# design.net
KiCad netlist of a schematic drawn in Altium Designer
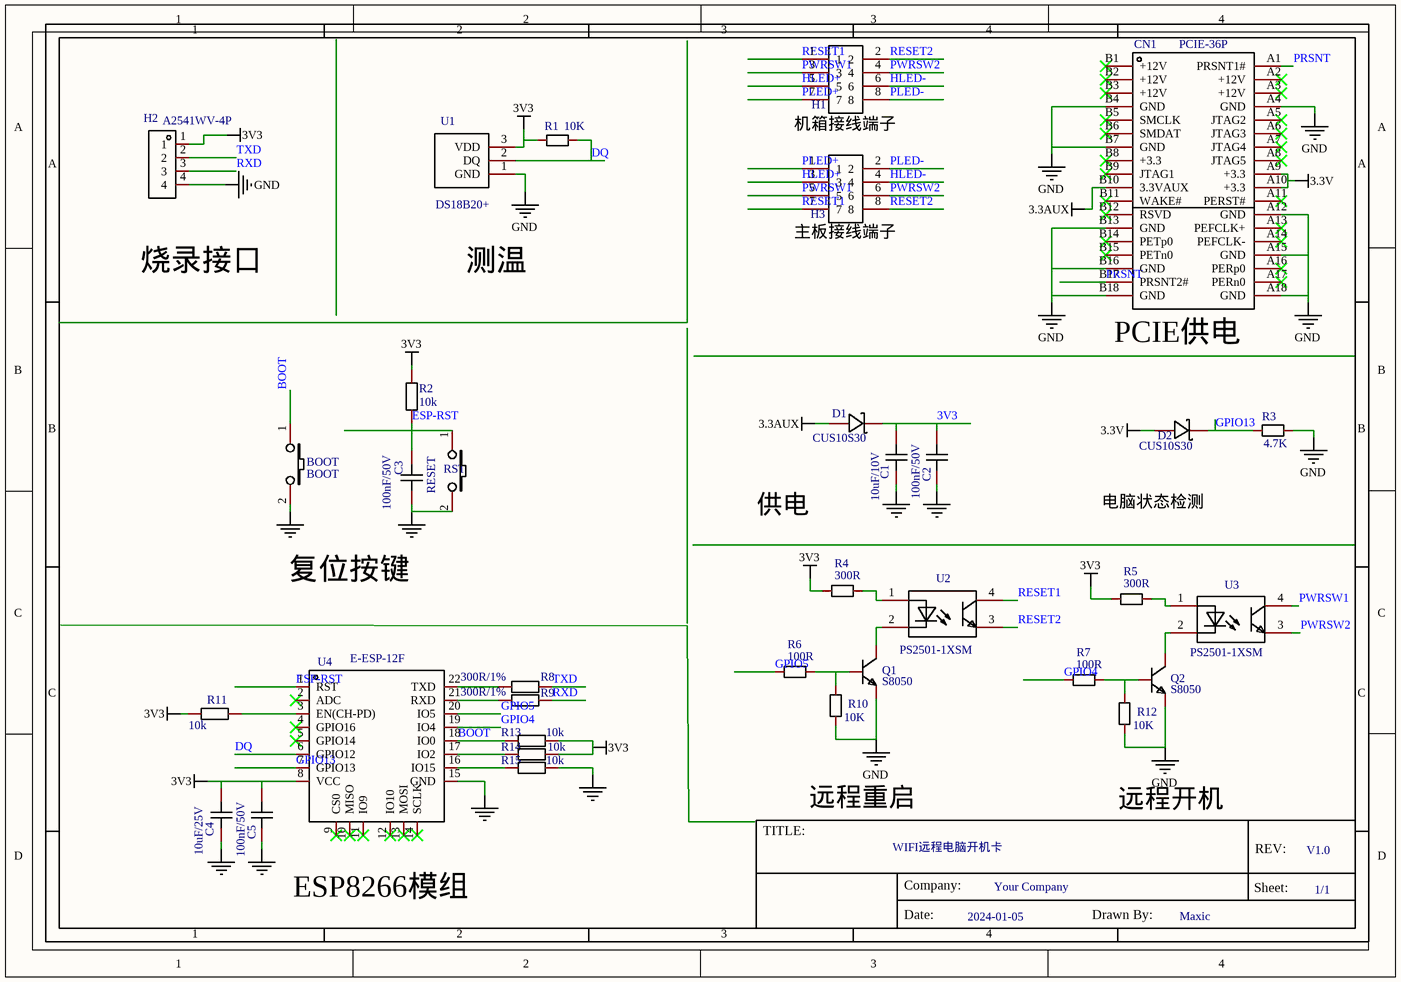
[diagram p0: 远程开机卡.schdoc]

(export (version "E")
  (design (tool "Eeschema 10.0.6"))
  (components
    (comp (ref "BOOT")
      (value "BOOT")
      (fields
        (field (name "NAME") "BOOT")
        (field (name "MANUFACTURER") "HRO")
        (field (name "MANUFACTURER PART") "K2-1107ST")
      )
      (libsource (lib "altium-import") (part "root_3_BOOT_"))
    )
    (comp (ref "C1")
      (value "10uF/10V")
      (fields
        (field (name "NAME") "10uF/10V")
        (field (name "MANUFACTURER") "Murata Electronics")
        (field (name "MANUFACTURER PART") "GRM188B31A106ME69D")
      )
      (libsource (lib "altium-import") (part "root_1_10uF/10V_"))
    )
    (comp (ref "C2")
      (value "100nF/50V")
      (fields
        (field (name "NAME") "100nF/50V")
        (field (name "MANUFACTURER") "Darfon Elec")
        (field (name "MANUFACTURER PART") "C1608X7R104KGTS")
      )
      (libsource (lib "altium-import") (part "root_1_100nF/50V_"))
    )
    (comp (ref "C3")
      (value "100nF/50V")
      (fields
        (field (name "NAME") "100nF/50V")
        (field (name "MANUFACTURER") "Darfon Elec")
        (field (name "MANUFACTURER PART") "C1608X7R104KGTS")
      )
      (libsource (lib "altium-import") (part "root_1_100nF/50V_"))
    )
    (comp (ref "C4")
      (value "10uF/25V")
      (fields
        (field (name "NAME") "10uF/25V")
        (field (name "MANUFACTURER") "TDK")
        (field (name "MANUFACTURER PART") "C1608X5R1E106MT000E")
      )
      (libsource (lib "altium-import") (part "root_1_10uF/25V_"))
    )
    (comp (ref "C5")
      (value "100nF/50V")
      (fields
        (field (name "NAME") "100nF/50V")
        (field (name "MANUFACTURER") "Darfon Elec")
        (field (name "MANUFACTURER PART") "C1608X7R104KGTS")
      )
      (libsource (lib "altium-import") (part "root_1_100nF/50V_"))
    )
    (comp (ref "CN1")
      (value "PCIE-36P")
      (fields (field (name "NAME") "PCIE-36P") (field (name "MANUFACTURER") "UMAX"))
      (libsource (lib "altium-import") (part "root_0_PCIE-36P_"))
    )
    (comp (ref "D1")
      (value "CUS10S30")
      (fields
        (field (name "NAME") "CUS10S30")
        (field (name "MANUFACTURER") "TOSHIBA")
        (field (name "MANUFACTURER PART") "CUS10S30 H3F")
      )
      (libsource (lib "altium-import") (part "root_2_CUS10S30_"))
    )
    (comp (ref "D2")
      (value "CUS10S30")
      (fields
        (field (name "NAME") "CUS10S30")
        (field (name "MANUFACTURER") "TOSHIBA")
        (field (name "MANUFACTURER PART") "CUS10S30 H3F")
      )
      (libsource (lib "altium-import") (part "root_2_CUS10S30_"))
    )
    (comp (ref "H1")
      (value "机箱接线端子")
      (fields (field (name "MANUFACTURER") "Shenzhen Cankemeng"))
      (libsource (lib "altium-import") (part "root_0_机箱接线端子_"))
    )
    (comp (ref "H2")
      (value "A2541WV-4P")
      (fields (field (name "NAME") "A2541WV-4P") (field (name "MANUFACTURER") "CJT(长江连接器)"))
      (libsource (lib "altium-import") (part "root_1_A2541WV-4P_"))
    )
    (comp (ref "H3")
      (value "主板接线端子")
      (fields (field (name "MANUFACTURER") "Shenzhen Cankemeng"))
      (libsource (lib "altium-import") (part "root_0_主板接线端子_"))
    )
    (comp (ref "Q1")
      (value "S8050")
      (fields (field (name "NAME") "S8050") (field (name "MANUFACTURER") "CJ"))
      (libsource (lib "altium-import") (part "root_0_S8050_"))
    )
    (comp (ref "Q2")
      (value "S8050")
      (fields (field (name "NAME") "S8050") (field (name "MANUFACTURER") "CJ"))
      (libsource (lib "altium-import") (part "root_0_S8050_"))
    )
    (comp (ref "R1")
      (value "10K")
      (fields (field (name "NAME") "10K") (field (name "MANUFACTURER") "ResistorToday"))
      (libsource (lib "altium-import") (part "root_2_10K_"))
    )
    (comp (ref "R2")
      (value "10k")
      (fields
        (field (name "NAME") "10k")
        (field (name "MANUFACTURER") "KOA Speer Elec")
        (field (name "MANUFACTURER PART") "RK73G1JTTD1002F")
      )
      (libsource (lib "altium-import") (part "root_3_10k/1%_"))
    )
    (comp (ref "R3")
      (value "4.7K")
      (fields (field (name "NAME") "4.7K") (field (name "MANUFACTURER") "PANASONIC"))
      (libsource (lib "altium-import") (part "root_0_4.7K_"))
    )
    (comp (ref "R4")
      (value "300R")
      (fields (field (name "NAME") "300R") (field (name "MANUFACTURER") "ResistorToday"))
      (libsource (lib "altium-import") (part "root_0_300R_"))
    )
    (comp (ref "R5")
      (value "300R")
      (fields (field (name "NAME") "300R") (field (name "MANUFACTURER") "ResistorToday"))
      (libsource (lib "altium-import") (part "root_0_300R_"))
    )
    (comp (ref "R6")
      (value "100R")
      (fields (field (name "NAME") "100R") (field (name "MANUFACTURER") "YAGEO"))
      (libsource (lib "altium-import") (part "root_0_100R_"))
    )
    (comp (ref "R7")
      (value "100R")
      (fields (field (name "NAME") "100R") (field (name "MANUFACTURER") "YAGEO"))
      (libsource (lib "altium-import") (part "root_0_100R_"))
    )
    (comp (ref "R8")
      (value "300R/1%")
      (fields
        (field (name "NAME") "300R/1%")
        (field (name "MANUFACTURER") "YAGEO")
        (field (name "MANUFACTURER PART") "AC0603FR-07300RL")
      )
      (libsource (lib "altium-import") (part "root_2_300R/1%_"))
    )
    (comp (ref "R9")
      (value "300R/1%")
      (fields
        (field (name "NAME") "300R/1%")
        (field (name "MANUFACTURER") "YAGEO")
        (field (name "MANUFACTURER PART") "AC0603FR-07300RL")
      )
      (libsource (lib "altium-import") (part "root_2_300R/1%_"))
    )
    (comp (ref "R10")
      (value "10K")
      (fields (field (name "NAME") "10K") (field (name "MANUFACTURER") "Stackpole Elec"))
      (libsource (lib "altium-import") (part "root_3_10K_"))
    )
    (comp (ref "R11")
      (value "10k")
      (fields
        (field (name "NAME") "10k")
        (field (name "MANUFACTURER") "KOA Speer Elec")
        (field (name "MANUFACTURER PART") "RK73G1JTTD1002F")
      )
      (libsource (lib "altium-import") (part "root_2_10k/1%_"))
    )
    (comp (ref "R12")
      (value "10K")
      (fields (field (name "NAME") "10K") (field (name "MANUFACTURER") "Stackpole Elec"))
      (libsource (lib "altium-import") (part "root_3_10K_"))
    )
    (comp (ref "R13")
      (value "10k")
      (fields
        (field (name "NAME") "10k")
        (field (name "MANUFACTURER") "KOA Speer Elec")
        (field (name "MANUFACTURER PART") "RK73G1JTTD1002F")
      )
      (libsource (lib "altium-import") (part "root_0_10k/1%_"))
    )
    (comp (ref "R14")
      (value "10k")
      (fields
        (field (name "NAME") "10k")
        (field (name "MANUFACTURER") "KOA Speer Elec")
        (field (name "MANUFACTURER PART") "RK73G1JTTD1002F")
      )
      (libsource (lib "altium-import") (part "root_2_10k/1%_"))
    )
    (comp (ref "R15")
      (value "10k")
      (fields
        (field (name "NAME") "10k")
        (field (name "MANUFACTURER") "KOA Speer Elec")
        (field (name "MANUFACTURER PART") "RK73G1JTTD1002F")
      )
      (libsource (lib "altium-import") (part "root_2_10k/1%_"))
    )
    (comp (ref "RST")
      (value "RESET")
      (fields
        (field (name "NAME") "RESET")
        (field (name "MANUFACTURER") "HRO")
        (field (name "MANUFACTURER PART") "K2-1107ST")
      )
      (libsource (lib "altium-import") (part "root_3_RESET_"))
    )
    (comp (ref "U1")
      (value "DS18B20+")
      (fields (field (name "NAME") "DS18B20+") (field (name "MANUFACTURER") "ADI(亚德诺)/MAXIM(美信)"))
      (libsource (lib "altium-import") (part "root_2_DS18B20+_"))
    )
    (comp (ref "U2")
      (value "PS2501-1XSM")
      (fields (field (name "NAME") "PS2501-1XSM") (field (name "MANUFACTURER") "ISOCOM(英国安数光)"))
      (libsource (lib "altium-import") (part "root_0_PS2501-1XSM_"))
    )
    (comp (ref "U3")
      (value "PS2501-1XSM")
      (fields (field (name "NAME") "PS2501-1XSM") (field (name "MANUFACTURER") "ISOCOM(英国安数光)"))
      (libsource (lib "altium-import") (part "root_0_PS2501-1XSM_"))
    )
    (comp (ref "U4")
      (value "E-ESP-12F")
      (fields
        (field (name "NAME") "E-ESP-12F")
        (field (name "MANUFACTURER PART") "ESP-12F(ESP8266MOD)")
        (field (name "MANUFACTURER") "Ai-Thinker")
      )
      (libsource (lib "altium-import") (part "root_0_E-ESP-12F_"))
    )
  )
  (nets
    (net (code "1") (name "/BOOT") (class "Default")
      (node (ref "BOOT") (pin "1") (pinfunction "1_1") (pintype "passive"))
      (node (ref "R13") (pin "1") (pinfunction "1_1") (pintype "passive"))
      (node (ref "U4") (pin "18") (pinfunction "IO0_18") (pintype "passive"))
    )
    (net (code "2") (name "/DQ") (class "Default")
      (node (ref "R1") (pin "1") (pinfunction "1_1") (pintype "passive"))
      (node (ref "U1") (pin "2") (pinfunction "DQ_2") (pintype "passive"))
      (node (ref "U4") (pin "6") (pinfunction "GPIO12_6") (pintype "passive"))
    )
    (net (code "3") (name "/ESP-RST") (class "Default")
      (node (ref "C3") (pin "2") (pinfunction "2_2") (pintype "passive"))
      (node (ref "R2") (pin "2") (pinfunction "2_2") (pintype "passive"))
      (node (ref "RST") (pin "1") (pinfunction "1_1") (pintype "passive"))
      (node (ref "U4") (pin "1") (pinfunction "RST_1") (pintype "passive"))
    )
    (net (code "4") (name "/GPIO4") (class "Default")
      (node (ref "R7") (pin "1") (pinfunction "1_1") (pintype "passive"))
      (node (ref "U4") (pin "19") (pinfunction "IO4_19") (pintype "passive"))
    )
    (net (code "5") (name "/GPIO5") (class "Default")
      (node (ref "R6") (pin "1") (pinfunction "1_1") (pintype "passive"))
      (node (ref "U4") (pin "20") (pinfunction "IO5_20") (pintype "passive"))
    )
    (net (code "6") (name "/GPIO13") (class "Default")
      (node (ref "D2") (pin "1") (pinfunction "K_1") (pintype "passive"))
      (node (ref "R3") (pin "1") (pinfunction "1_1") (pintype "passive"))
      (node (ref "U4") (pin "7") (pinfunction "GPIO13_7") (pintype "passive"))
    )
    (net (code "7") (name "/HLED+") (class "Default")
      (node (ref "H1") (pin "5") (pinfunction "5_5") (pintype "passive"))
      (node (ref "H3") (pin "3") (pinfunction "3_3") (pintype "passive"))
    )
    (net (code "8") (name "/HLED-") (class "Default")
      (node (ref "H1") (pin "6") (pinfunction "6_6") (pintype "passive"))
      (node (ref "H3") (pin "4") (pinfunction "4_4") (pintype "passive"))
    )
    (net (code "9") (name "/PLED+") (class "Default")
      (node (ref "H1") (pin "7") (pinfunction "7_7") (pintype "passive"))
      (node (ref "H3") (pin "1") (pinfunction "1_1") (pintype "passive"))
    )
    (net (code "10") (name "/PLED-") (class "Default")
      (node (ref "H1") (pin "8") (pinfunction "8_8") (pintype "passive"))
      (node (ref "H3") (pin "2") (pinfunction "2_2") (pintype "passive"))
    )
    (net (code "11") (name "/PRSNT") (class "Default")
      (node (ref "CN1") (pin "A1") (pinfunction "PRSNT1#_A1") (pintype "passive"))
      (node (ref "CN1") (pin "B17") (pinfunction "PRSNT2#_B17") (pintype "passive"))
    )
    (net (code "12") (name "/PWRSW1") (class "Default")
      (node (ref "H1") (pin "3") (pinfunction "3_3") (pintype "passive"))
      (node (ref "H3") (pin "5") (pinfunction "5_5") (pintype "passive"))
      (node (ref "U3") (pin "4") (pinfunction "Collector_4") (pintype "passive"))
    )
    (net (code "13") (name "/PWRSW2") (class "Default")
      (node (ref "H1") (pin "4") (pinfunction "4_4") (pintype "passive"))
      (node (ref "H3") (pin "6") (pinfunction "6_6") (pintype "passive"))
      (node (ref "U3") (pin "3") (pinfunction "Emitter_3") (pintype "passive"))
    )
    (net (code "14") (name "/RESET1") (class "Default")
      (node (ref "H1") (pin "1") (pinfunction "1_1") (pintype "passive"))
      (node (ref "H3") (pin "7") (pinfunction "7_7") (pintype "passive"))
      (node (ref "U2") (pin "4") (pinfunction "Collector_4") (pintype "passive"))
    )
    (net (code "15") (name "/RESET2") (class "Default")
      (node (ref "H1") (pin "2") (pinfunction "2_2") (pintype "passive"))
      (node (ref "H3") (pin "8") (pinfunction "8_8") (pintype "passive"))
      (node (ref "U2") (pin "3") (pinfunction "Emitter_3") (pintype "passive"))
    )
    (net (code "16") (name "/RXD") (class "Default")
      (node (ref "H2") (pin "3") (pinfunction "3_3") (pintype "passive"))
      (node (ref "R9") (pin "1") (pinfunction "1_1") (pintype "passive"))
    )
    (net (code "17") (name "/TXD") (class "Default")
      (node (ref "H2") (pin "2") (pinfunction "2_2") (pintype "passive"))
      (node (ref "R8") (pin "1") (pinfunction "1_1") (pintype "passive"))
    )
    (net (code "18") (name "3.3AUX") (class "Default")
      (node (ref "CN1") (pin "B10") (pinfunction "3.3VAUX_B10") (pintype "passive"))
      (node (ref "D1") (pin "2") (pinfunction "A_2") (pintype "passive"))
    )
    (net (code "19") (name "3.3V") (class "Default")
      (node (ref "CN1") (pin "A10") (pinfunction "+3.3_A10") (pintype "passive"))
      (node (ref "CN1") (pin "A9") (pinfunction "+3.3_A9") (pintype "passive"))
      (node (ref "D2") (pin "2") (pinfunction "A_2") (pintype "passive"))
    )
    (net (code "20") (name "3V3") (class "Default")
      (node (ref "C1") (pin "2") (pinfunction "2_2") (pintype "passive"))
      (node (ref "C2") (pin "2") (pinfunction "2_2") (pintype "passive"))
      (node (ref "C4") (pin "2") (pinfunction "2_2") (pintype "passive"))
      (node (ref "C5") (pin "2") (pinfunction "2_2") (pintype "passive"))
      (node (ref "D1") (pin "1") (pinfunction "K_1") (pintype "passive"))
      (node (ref "H2") (pin "1") (pinfunction "1_1") (pintype "passive"))
      (node (ref "R1") (pin "2") (pinfunction "2_2") (pintype "passive"))
      (node (ref "R11") (pin "2") (pinfunction "2_2") (pintype "passive"))
      (node (ref "R13") (pin "2") (pinfunction "2_2") (pintype "passive"))
      (node (ref "R14") (pin "1") (pinfunction "1_1") (pintype "passive"))
      (node (ref "R2") (pin "1") (pinfunction "1_1") (pintype "passive"))
      (node (ref "R4") (pin "1") (pinfunction "1_1") (pintype "passive"))
      (node (ref "R5") (pin "1") (pinfunction "1_1") (pintype "passive"))
      (node (ref "U1") (pin "3") (pinfunction "VDD_3") (pintype "passive"))
      (node (ref "U4") (pin "8") (pinfunction "VCC_8") (pintype "passive"))
    )
    (net (code "21") (name "GND") (class "Default")
      (node (ref "BOOT") (pin "2") (pinfunction "2_2") (pintype "passive"))
      (node (ref "C1") (pin "1") (pinfunction "1_1") (pintype "passive"))
      (node (ref "C2") (pin "1") (pinfunction "1_1") (pintype "passive"))
      (node (ref "C3") (pin "1") (pinfunction "1_1") (pintype "passive"))
      (node (ref "C4") (pin "1") (pinfunction "1_1") (pintype "passive"))
      (node (ref "C5") (pin "1") (pinfunction "1_1") (pintype "passive"))
      (node (ref "CN1") (pin "A12") (pinfunction "GND_A12") (pintype "passive"))
      (node (ref "CN1") (pin "A15") (pinfunction "GND_A15") (pintype "passive"))
      (node (ref "CN1") (pin "A18") (pinfunction "GND_A18") (pintype "passive"))
      (node (ref "CN1") (pin "A4") (pinfunction "GND_A4") (pintype "passive"))
      (node (ref "CN1") (pin "B13") (pinfunction "GND_B13") (pintype "passive"))
      (node (ref "CN1") (pin "B16") (pinfunction "GND_B16") (pintype "passive"))
      (node (ref "CN1") (pin "B18") (pinfunction "GND_B18") (pintype "passive"))
      (node (ref "CN1") (pin "B4") (pinfunction "GND_B4") (pintype "passive"))
      (node (ref "CN1") (pin "B7") (pinfunction "GND_B7") (pintype "passive"))
      (node (ref "H2") (pin "4") (pinfunction "4_4") (pintype "passive"))
      (node (ref "Q1") (pin "2") (pinfunction "2_2") (pintype "passive"))
      (node (ref "Q2") (pin "2") (pinfunction "2_2") (pintype "passive"))
      (node (ref "R10") (pin "2") (pinfunction "2_2") (pintype "passive"))
      (node (ref "R12") (pin "2") (pinfunction "2_2") (pintype "passive"))
      (node (ref "R15") (pin "1") (pinfunction "1_1") (pintype "passive"))
      (node (ref "R3") (pin "2") (pinfunction "2_2") (pintype "passive"))
      (node (ref "RST") (pin "2") (pinfunction "2_2") (pintype "passive"))
      (node (ref "U1") (pin "1") (pinfunction "GND_1") (pintype "passive"))
      (node (ref "U4") (pin "15") (pinfunction "GND_15") (pintype "passive"))
    )
    (net (code "22") (name "Net-(Q1-Pad1)") (class "Default")
      (node (ref "Q1") (pin "1") (pinfunction "1_1") (pintype "passive"))
      (node (ref "R10") (pin "1") (pinfunction "1_1") (pintype "passive"))
      (node (ref "R6") (pin "2") (pinfunction "2_2") (pintype "passive"))
    )
    (net (code "23") (name "Net-(Q2-Pad1)") (class "Default")
      (node (ref "Q2") (pin "1") (pinfunction "1_1") (pintype "passive"))
      (node (ref "R12") (pin "1") (pinfunction "1_1") (pintype "passive"))
      (node (ref "R7") (pin "2") (pinfunction "2_2") (pintype "passive"))
    )
    (net (code "24") (name "Net-(U2-Anode)") (class "Default")
      (node (ref "R4") (pin "2") (pinfunction "2_2") (pintype "passive"))
      (node (ref "U2") (pin "1") (pinfunction "Anode_1") (pintype "passive"))
    )
    (net (code "25") (name "Net-(U2-Cathode)") (class "Default")
      (node (ref "Q1") (pin "3") (pinfunction "3_3") (pintype "passive"))
      (node (ref "U2") (pin "2") (pinfunction "Cathode_2") (pintype "passive"))
    )
    (net (code "26") (name "Net-(U3-Anode)") (class "Default")
      (node (ref "R5") (pin "2") (pinfunction "2_2") (pintype "passive"))
      (node (ref "U3") (pin "1") (pinfunction "Anode_1") (pintype "passive"))
    )
    (net (code "27") (name "Net-(U3-Cathode)") (class "Default")
      (node (ref "Q2") (pin "3") (pinfunction "3_3") (pintype "passive"))
      (node (ref "U3") (pin "2") (pinfunction "Cathode_2") (pintype "passive"))
    )
    (net (code "28") (name "Net-(U4-EN(CH-PD))") (class "Default")
      (node (ref "R11") (pin "1") (pinfunction "1_1") (pintype "passive"))
      (node (ref "U4") (pin "3") (pinfunction "EN(CH-PD)_3") (pintype "passive"))
    )
    (net (code "29") (name "Net-(U4-IO2)") (class "Default")
      (node (ref "R14") (pin "2") (pinfunction "2_2") (pintype "passive"))
      (node (ref "U4") (pin "17") (pinfunction "IO2_17") (pintype "passive"))
    )
    (net (code "30") (name "Net-(U4-IO15)") (class "Default")
      (node (ref "R15") (pin "2") (pinfunction "2_2") (pintype "passive"))
      (node (ref "U4") (pin "16") (pinfunction "IO15_16") (pintype "passive"))
    )
    (net (code "31") (name "Net-(U4-RXD)") (class "Default")
      (node (ref "R9") (pin "2") (pinfunction "2_2") (pintype "passive"))
      (node (ref "U4") (pin "21") (pinfunction "RXD_21") (pintype "passive"))
    )
    (net (code "32") (name "Net-(U4-TXD)") (class "Default")
      (node (ref "R8") (pin "2") (pinfunction "2_2") (pintype "passive"))
      (node (ref "U4") (pin "22") (pinfunction "TXD_22") (pintype "passive"))
    )
    (net (code "33") (name "unconnected-(CN1-+3.3-PadB8)") (class "Default")
      (node (ref "CN1") (pin "B8") (pinfunction "+3.3_B8") (pintype "passive+no_connect"))
    )
    (net (code "34") (name "unconnected-(CN1-+12V-PadA2)") (class "Default")
      (node (ref "CN1") (pin "A2") (pinfunction "+12V_A2") (pintype "passive+no_connect"))
    )
    (net (code "35") (name "unconnected-(CN1-+12V-PadA3)") (class "Default")
      (node (ref "CN1") (pin "A3") (pinfunction "+12V_A3") (pintype "passive+no_connect"))
    )
    (net (code "36") (name "unconnected-(CN1-+12V-PadB1)") (class "Default")
      (node (ref "CN1") (pin "B1") (pinfunction "+12V_B1") (pintype "passive+no_connect"))
    )
    (net (code "37") (name "unconnected-(CN1-+12V-PadB2)") (class "Default")
      (node (ref "CN1") (pin "B2") (pinfunction "+12V_B2") (pintype "passive+no_connect"))
    )
    (net (code "38") (name "unconnected-(CN1-+12V-PadB3)") (class "Default")
      (node (ref "CN1") (pin "B3") (pinfunction "+12V_B3") (pintype "passive+no_connect"))
    )
    (net (code "39") (name "unconnected-(CN1-JTAG1-PadB9)") (class "Default")
      (node (ref "CN1") (pin "B9") (pinfunction "JTAG1_B9") (pintype "passive+no_connect"))
    )
    (net (code "40") (name "unconnected-(CN1-JTAG2-PadA5)") (class "Default")
      (node (ref "CN1") (pin "A5") (pinfunction "JTAG2_A5") (pintype "passive+no_connect"))
    )
    (net (code "41") (name "unconnected-(CN1-JTAG3-PadA6)") (class "Default")
      (node (ref "CN1") (pin "A6") (pinfunction "JTAG3_A6") (pintype "passive+no_connect"))
    )
    (net (code "42") (name "unconnected-(CN1-JTAG4-PadA7)") (class "Default")
      (node (ref "CN1") (pin "A7") (pinfunction "JTAG4_A7") (pintype "passive+no_connect"))
    )
    (net (code "43") (name "unconnected-(CN1-JTAG5-PadA8)") (class "Default")
      (node (ref "CN1") (pin "A8") (pinfunction "JTAG5_A8") (pintype "passive+no_connect"))
    )
    (net (code "44") (name "unconnected-(CN1-PEFCLK+-PadA13)") (class "Default")
      (node (ref "CN1") (pin "A13") (pinfunction "PEFCLK+_A13") (pintype "passive+no_connect"))
    )
    (net (code "45") (name "unconnected-(CN1-PEFCLK--PadA14)") (class "Default")
      (node (ref "CN1") (pin "A14") (pinfunction "PEFCLK-_A14") (pintype "passive+no_connect"))
    )
    (net (code "46") (name "unconnected-(CN1-PERST#-PadA11)") (class "Default")
      (node (ref "CN1") (pin "A11") (pinfunction "PERST#_A11") (pintype "passive+no_connect"))
    )
    (net (code "47") (name "unconnected-(CN1-PERn0-PadA17)") (class "Default")
      (node (ref "CN1") (pin "A17") (pinfunction "PERn0_A17") (pintype "passive+no_connect"))
    )
    (net (code "48") (name "unconnected-(CN1-PERp0-PadA16)") (class "Default")
      (node (ref "CN1") (pin "A16") (pinfunction "PERp0_A16") (pintype "passive+no_connect"))
    )
    (net (code "49") (name "unconnected-(CN1-PETn0-PadB15)") (class "Default")
      (node (ref "CN1") (pin "B15") (pinfunction "PETn0_B15") (pintype "passive+no_connect"))
    )
    (net (code "50") (name "unconnected-(CN1-PETp0-PadB14)") (class "Default")
      (node (ref "CN1") (pin "B14") (pinfunction "PETp0_B14") (pintype "passive+no_connect"))
    )
    (net (code "51") (name "unconnected-(CN1-RSVD-PadB12)") (class "Default")
      (node (ref "CN1") (pin "B12") (pinfunction "RSVD_B12") (pintype "passive+no_connect"))
    )
    (net (code "52") (name "unconnected-(CN1-SMCLK-PadB5)") (class "Default")
      (node (ref "CN1") (pin "B5") (pinfunction "SMCLK_B5") (pintype "passive+no_connect"))
    )
    (net (code "53") (name "unconnected-(CN1-SMDAT-PadB6)") (class "Default")
      (node (ref "CN1") (pin "B6") (pinfunction "SMDAT_B6") (pintype "passive+no_connect"))
    )
    (net (code "54") (name "unconnected-(CN1-WAKE#-PadB11)") (class "Default")
      (node (ref "CN1") (pin "B11") (pinfunction "WAKE#_B11") (pintype "passive+no_connect"))
    )
    (net (code "55") (name "unconnected-(U4-ADC-Pad2)") (class "Default")
      (node (ref "U4") (pin "2") (pinfunction "ADC_2") (pintype "passive+no_connect"))
    )
    (net (code "56") (name "unconnected-(U4-CS0-Pad9)") (class "Default")
      (node (ref "U4") (pin "9") (pinfunction "CS0_9") (pintype "passive+no_connect"))
    )
    (net (code "57") (name "unconnected-(U4-GPIO14-Pad5)") (class "Default")
      (node (ref "U4") (pin "5") (pinfunction "GPIO14_5") (pintype "passive+no_connect"))
    )
    (net (code "58") (name "unconnected-(U4-GPIO16-Pad4)") (class "Default")
      (node (ref "U4") (pin "4") (pinfunction "GPIO16_4") (pintype "passive+no_connect"))
    )
    (net (code "59") (name "unconnected-(U4-IO9-Pad11)") (class "Default")
      (node (ref "U4") (pin "11") (pinfunction "IO9_11") (pintype "passive+no_connect"))
    )
    (net (code "60") (name "unconnected-(U4-IO10-Pad12)") (class "Default")
      (node (ref "U4") (pin "12") (pinfunction "IO10_12") (pintype "passive+no_connect"))
    )
    (net (code "61") (name "unconnected-(U4-MISO-Pad10)") (class "Default")
      (node (ref "U4") (pin "10") (pinfunction "MISO_10") (pintype "passive+no_connect"))
    )
    (net (code "62") (name "unconnected-(U4-MOSI-Pad13)") (class "Default")
      (node (ref "U4") (pin "13") (pinfunction "MOSI_13") (pintype "passive+no_connect"))
    )
    (net (code "63") (name "unconnected-(U4-SCLK-Pad14)") (class "Default")
      (node (ref "U4") (pin "14") (pinfunction "SCLK_14") (pintype "passive+no_connect"))
    )
  )
)
